# sb-sonata-fpgaio2.net
KiCad netlist of a schematic drawn in Altium Designer
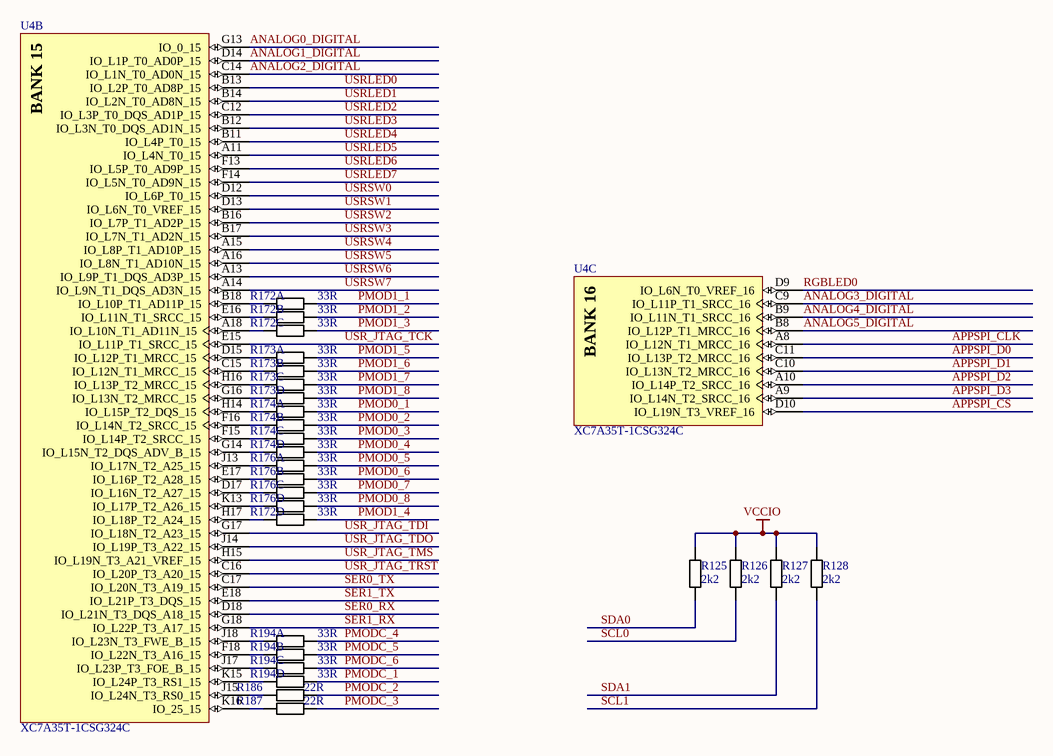
[diagram p0: sb-sonata-fpgaio2.SchDoc]

(export (version "E")
  (design (tool "Eeschema 10.0.6"))
  (components
    (comp (ref "R125")
      (value "2k2")
      (footprint "RESC1608X55N")
      (description "2k2 res, 0603, 1%, 1/10W")
      (fields (field (name "PART NUMBER") "RCHIP-2K2-0603") (field (name "TOLERANCE") "1%"))
      (libsource (lib "NewAE_AltiumLib") (part "RES-EU"))
    )
    (comp (ref "R126")
      (value "2k2")
      (footprint "RESC1608X55N")
      (description "2k2 res, 0603, 1%, 1/10W")
      (fields (field (name "PART NUMBER") "RCHIP-2K2-0603") (field (name "TOLERANCE") "1%"))
      (libsource (lib "NewAE_AltiumLib") (part "RES-EU"))
    )
    (comp (ref "R127")
      (value "2k2")
      (footprint "RESC1608X55N")
      (description "2k2 res, 0603, 1%, 1/10W")
      (fields (field (name "PART NUMBER") "RCHIP-2K2-0603") (field (name "TOLERANCE") "1%"))
      (libsource (lib "NewAE_AltiumLib") (part "RES-EU"))
    )
    (comp (ref "R128")
      (value "2k2")
      (footprint "RESC1608X55N")
      (description "2k2 res, 0603, 1%, 1/10W")
      (fields (field (name "PART NUMBER") "RCHIP-2K2-0603") (field (name "TOLERANCE") "1%"))
      (libsource (lib "NewAE_AltiumLib") (part "RES-EU"))
    )
    (comp (ref "R172")
      (value "33R")
      (footprint "741C083")
      (description "33-ohm, 0.5mm res array")
      (fields (field (name "PART NUMBER") "741C083330JP"))
      (libsource (lib "NewAE_AltiumLib") (part "RES-EU-4ARRAY"))
    )
    (comp (ref "R173")
      (value "33R")
      (footprint "741C083")
      (description "33-ohm, 0.5mm res array")
      (fields (field (name "PART NUMBER") "741C083330JP"))
      (libsource (lib "NewAE_AltiumLib") (part "RES-EU-4ARRAY"))
    )
    (comp (ref "R174")
      (value "33R")
      (footprint "741C083")
      (description "33-ohm, 0.5mm res array")
      (fields (field (name "PART NUMBER") "741C083330JP"))
      (libsource (lib "NewAE_AltiumLib") (part "RES-EU-4ARRAY"))
    )
    (comp (ref "R176")
      (value "33R")
      (footprint "741C083")
      (description "33-ohm, 0.5mm res array")
      (fields (field (name "PART NUMBER") "741C083330JP"))
      (libsource (lib "NewAE_AltiumLib") (part "RES-EU-4ARRAY"))
    )
    (comp (ref "R186")
      (value "22R")
      (footprint "RESC1005X40N")
      (description "22R res, 0402, 1%, 1/16W")
      (fields (field (name "PART NUMBER") "RCHIP-22R-0402") (field (name "TOLERANCE") "1%"))
      (libsource (lib "") (part "RES-EU_1"))
    )
    (comp (ref "R187")
      (value "22R")
      (footprint "RESC1005X40N")
      (description "22R res, 0402, 1%, 1/16W")
      (fields (field (name "PART NUMBER") "RCHIP-22R-0402") (field (name "TOLERANCE") "1%"))
      (libsource (lib "") (part "RES-EU_1"))
    )
    (comp (ref "R194")
      (value "33R")
      (footprint "741C083")
      (description "33-ohm, 0.5mm res array")
      (fields (field (name "PART NUMBER") "741C083330JP"))
      (libsource (lib "NewAE_AltiumLib") (part "RES-EU-4ARRAY"))
    )
    (comp (ref "U4")
      (value "XC7A35T-1CSG324C")
      (footprint "CSG324")
      (description "Artix-7 FPGA, 210 User I/Os, 0 GTP, 324-Ball BGA, Speed Grade 1, Commercial Grade, Pb-Free")
      (fields (field (name "MANUFACTURER") "Xilinx"))
      (libsource (lib "") (part "XLNX-XC7A35T-CSG324_1"))
    )
  )
  (nets
    (net (code "1") (name "/ANALOG0_DIGITAL") (class "Default")
      (node (ref "U4") (pin "G13") (pinfunction "IO_0_15_G13") (pintype "bidirectional"))
    )
    (net (code "2") (name "/ANALOG1_DIGITAL") (class "Default")
      (node (ref "U4") (pin "D14") (pinfunction "IO_L1P_T0_AD0P_15_D14") (pintype "bidirectional"))
    )
    (net (code "3") (name "/ANALOG2_DIGITAL") (class "Default")
      (node (ref "U4") (pin "C14") (pinfunction "IO_L1N_T0_AD0N_15_C14") (pintype "bidirectional"))
    )
    (net (code "4") (name "/ANALOG3_DIGITAL") (class "Default")
      (node (ref "U4") (pin "C9") (pinfunction "IO_L11P_T1_SRCC_16_C9") (pintype "bidirectional"))
    )
    (net (code "5") (name "/ANALOG4_DIGITAL") (class "Default")
      (node (ref "U4") (pin "B9") (pinfunction "IO_L11N_T1_SRCC_16_B9") (pintype "bidirectional"))
    )
    (net (code "6") (name "/ANALOG5_DIGITAL") (class "Default")
      (node (ref "U4") (pin "B8") (pinfunction "IO_L12P_T1_MRCC_16_B8") (pintype "bidirectional"))
    )
    (net (code "7") (name "/APPSPI_CLK") (class "Default")
      (node (ref "U4") (pin "A8") (pinfunction "IO_L12N_T1_MRCC_16_A8") (pintype "bidirectional"))
    )
    (net (code "8") (name "/APPSPI_CS") (class "Default")
      (node (ref "U4") (pin "D10") (pinfunction "IO_L19N_T3_VREF_16_D10") (pintype "bidirectional"))
    )
    (net (code "9") (name "/APPSPI_D0") (class "Default")
      (node (ref "U4") (pin "C11") (pinfunction "IO_L13P_T2_MRCC_16_C11") (pintype "bidirectional"))
    )
    (net (code "10") (name "/APPSPI_D1") (class "Default")
      (node (ref "U4") (pin "C10") (pinfunction "IO_L13N_T2_MRCC_16_C10") (pintype "bidirectional"))
    )
    (net (code "11") (name "/APPSPI_D2") (class "Default")
      (node (ref "U4") (pin "A10") (pinfunction "IO_L14P_T2_SRCC_16_A10") (pintype "bidirectional"))
    )
    (net (code "12") (name "/APPSPI_D3") (class "Default")
      (node (ref "U4") (pin "A9") (pinfunction "IO_L14N_T2_SRCC_16_A9") (pintype "bidirectional"))
    )
    (net (code "13") (name "/PMOD0_1") (class "Default")
      (node (ref "R174") (pin "1B") (pinfunction "1B_1B") (pintype "passive"))
    )
    (net (code "14") (name "/PMOD0_2") (class "Default")
      (node (ref "R174") (pin "2B") (pinfunction "2B_2B") (pintype "passive"))
    )
    (net (code "15") (name "/PMOD0_3") (class "Default")
      (node (ref "R174") (pin "3B") (pinfunction "3B_3B") (pintype "passive"))
    )
    (net (code "16") (name "/PMOD0_4") (class "Default")
      (node (ref "R174") (pin "4B") (pinfunction "4B_4B") (pintype "passive"))
    )
    (net (code "17") (name "/PMOD0_5") (class "Default")
      (node (ref "R176") (pin "1B") (pinfunction "1B_1B") (pintype "passive"))
    )
    (net (code "18") (name "/PMOD0_6") (class "Default")
      (node (ref "R176") (pin "2B") (pinfunction "2B_2B") (pintype "passive"))
    )
    (net (code "19") (name "/PMOD0_7") (class "Default")
      (node (ref "R176") (pin "3B") (pinfunction "3B_3B") (pintype "passive"))
    )
    (net (code "20") (name "/PMOD0_8") (class "Default")
      (node (ref "R176") (pin "4B") (pinfunction "4B_4B") (pintype "passive"))
    )
    (net (code "21") (name "/PMOD1_1") (class "Default")
      (node (ref "R172") (pin "1B") (pinfunction "1B_1B") (pintype "passive"))
    )
    (net (code "22") (name "/PMOD1_2") (class "Default")
      (node (ref "R172") (pin "2B") (pinfunction "2B_2B") (pintype "passive"))
    )
    (net (code "23") (name "/PMOD1_3") (class "Default")
      (node (ref "R172") (pin "3B") (pinfunction "3B_3B") (pintype "passive"))
    )
    (net (code "24") (name "/PMOD1_4") (class "Default")
      (node (ref "R172") (pin "4B") (pinfunction "4B_4B") (pintype "passive"))
    )
    (net (code "25") (name "/PMOD1_5") (class "Default")
      (node (ref "R173") (pin "1B") (pinfunction "1B_1B") (pintype "passive"))
    )
    (net (code "26") (name "/PMOD1_6") (class "Default")
      (node (ref "R173") (pin "2B") (pinfunction "2B_2B") (pintype "passive"))
    )
    (net (code "27") (name "/PMOD1_7") (class "Default")
      (node (ref "R173") (pin "3B") (pinfunction "3B_3B") (pintype "passive"))
    )
    (net (code "28") (name "/PMOD1_8") (class "Default")
      (node (ref "R173") (pin "4B") (pinfunction "4B_4B") (pintype "passive"))
    )
    (net (code "29") (name "/PMODC_1") (class "Default")
      (node (ref "R194") (pin "4B") (pinfunction "4B_4B") (pintype "passive"))
    )
    (net (code "30") (name "/PMODC_2") (class "Default")
      (node (ref "R186") (pin "2") (pinfunction "2_2") (pintype "passive"))
    )
    (net (code "31") (name "/PMODC_3") (class "Default")
      (node (ref "R187") (pin "2") (pinfunction "2_2") (pintype "passive"))
    )
    (net (code "32") (name "/PMODC_4") (class "Default")
      (node (ref "R194") (pin "1B") (pinfunction "1B_1B") (pintype "passive"))
    )
    (net (code "33") (name "/PMODC_5") (class "Default")
      (node (ref "R194") (pin "2B") (pinfunction "2B_2B") (pintype "passive"))
    )
    (net (code "34") (name "/PMODC_6") (class "Default")
      (node (ref "R194") (pin "3B") (pinfunction "3B_3B") (pintype "passive"))
    )
    (net (code "35") (name "/RGBLED0") (class "Default")
      (node (ref "U4") (pin "D9") (pinfunction "IO_L6N_T0_VREF_16_D9") (pintype "bidirectional"))
    )
    (net (code "36") (name "/SCL0") (class "Default")
      (node (ref "R126") (pin "2") (pinfunction "2_2") (pintype "passive"))
    )
    (net (code "37") (name "/SCL1") (class "Default")
      (node (ref "R128") (pin "2") (pinfunction "2_2") (pintype "passive"))
    )
    (net (code "38") (name "/SDA0") (class "Default")
      (node (ref "R125") (pin "2") (pinfunction "2_2") (pintype "passive"))
    )
    (net (code "39") (name "/SDA1") (class "Default")
      (node (ref "R127") (pin "2") (pinfunction "2_2") (pintype "passive"))
    )
    (net (code "40") (name "/SER0_RX") (class "Default")
      (node (ref "U4") (pin "D18") (pinfunction "IO_L21N_T3_DQS_A18_15_D18") (pintype "bidirectional"))
    )
    (net (code "41") (name "/SER0_TX") (class "Default")
      (node (ref "U4") (pin "C17") (pinfunction "IO_L20N_T3_A19_15_C17") (pintype "bidirectional"))
    )
    (net (code "42") (name "/SER1_RX") (class "Default")
      (node (ref "U4") (pin "G18") (pinfunction "IO_L22P_T3_A17_15_G18") (pintype "bidirectional"))
    )
    (net (code "43") (name "/SER1_TX") (class "Default")
      (node (ref "U4") (pin "E18") (pinfunction "IO_L21P_T3_DQS_15_E18") (pintype "bidirectional"))
    )
    (net (code "44") (name "/USRLED0") (class "Default")
      (node (ref "U4") (pin "B13") (pinfunction "IO_L2P_T0_AD8P_15_B13") (pintype "bidirectional"))
    )
    (net (code "45") (name "/USRLED1") (class "Default")
      (node (ref "U4") (pin "B14") (pinfunction "IO_L2N_T0_AD8N_15_B14") (pintype "bidirectional"))
    )
    (net (code "46") (name "/USRLED2") (class "Default")
      (node (ref "U4") (pin "C12") (pinfunction "IO_L3P_T0_DQS_AD1P_15_C12") (pintype "bidirectional"))
    )
    (net (code "47") (name "/USRLED3") (class "Default")
      (node (ref "U4") (pin "B12") (pinfunction "IO_L3N_T0_DQS_AD1N_15_B12") (pintype "bidirectional"))
    )
    (net (code "48") (name "/USRLED4") (class "Default")
      (node (ref "U4") (pin "B11") (pinfunction "IO_L4P_T0_15_B11") (pintype "bidirectional"))
    )
    (net (code "49") (name "/USRLED5") (class "Default")
      (node (ref "U4") (pin "A11") (pinfunction "IO_L4N_T0_15_A11") (pintype "bidirectional"))
    )
    (net (code "50") (name "/USRLED6") (class "Default")
      (node (ref "U4") (pin "F13") (pinfunction "IO_L5P_T0_AD9P_15_F13") (pintype "bidirectional"))
    )
    (net (code "51") (name "/USRLED7") (class "Default")
      (node (ref "U4") (pin "F14") (pinfunction "IO_L5N_T0_AD9N_15_F14") (pintype "bidirectional"))
    )
    (net (code "52") (name "/USRSW0") (class "Default")
      (node (ref "U4") (pin "D12") (pinfunction "IO_L6P_T0_15_D12") (pintype "bidirectional"))
    )
    (net (code "53") (name "/USRSW1") (class "Default")
      (node (ref "U4") (pin "D13") (pinfunction "IO_L6N_T0_VREF_15_D13") (pintype "bidirectional"))
    )
    (net (code "54") (name "/USRSW2") (class "Default")
      (node (ref "U4") (pin "B16") (pinfunction "IO_L7P_T1_AD2P_15_B16") (pintype "bidirectional"))
    )
    (net (code "55") (name "/USRSW3") (class "Default")
      (node (ref "U4") (pin "B17") (pinfunction "IO_L7N_T1_AD2N_15_B17") (pintype "bidirectional"))
    )
    (net (code "56") (name "/USRSW4") (class "Default")
      (node (ref "U4") (pin "A15") (pinfunction "IO_L8P_T1_AD10P_15_A15") (pintype "bidirectional"))
    )
    (net (code "57") (name "/USRSW5") (class "Default")
      (node (ref "U4") (pin "A16") (pinfunction "IO_L8N_T1_AD10N_15_A16") (pintype "bidirectional"))
    )
    (net (code "58") (name "/USRSW6") (class "Default")
      (node (ref "U4") (pin "A13") (pinfunction "IO_L9P_T1_DQS_AD3P_15_A13") (pintype "bidirectional"))
    )
    (net (code "59") (name "/USRSW7") (class "Default")
      (node (ref "U4") (pin "A14") (pinfunction "IO_L9N_T1_DQS_AD3N_15_A14") (pintype "bidirectional"))
    )
    (net (code "60") (name "/USR_JTAG_TCK") (class "Default")
      (node (ref "U4") (pin "E15") (pinfunction "IO_L11P_T1_SRCC_15_E15") (pintype "bidirectional"))
    )
    (net (code "61") (name "/USR_JTAG_TDI") (class "Default")
      (node (ref "U4") (pin "G17") (pinfunction "IO_L18N_T2_A23_15_G17") (pintype "bidirectional"))
    )
    (net (code "62") (name "/USR_JTAG_TDO") (class "Default")
      (node (ref "U4") (pin "J14") (pinfunction "IO_L19P_T3_A22_15_J14") (pintype "bidirectional"))
    )
    (net (code "63") (name "/USR_JTAG_TMS") (class "Default")
      (node (ref "U4") (pin "H15") (pinfunction "IO_L19N_T3_A21_VREF_15_H15") (pintype "bidirectional"))
    )
    (net (code "64") (name "/USR_JTAG_TRST") (class "Default")
      (node (ref "U4") (pin "C16") (pinfunction "IO_L20P_T3_A20_15_C16") (pintype "bidirectional"))
    )
    (net (code "65") (name "Net-(U4B-IO_25_15)") (class "Default")
      (node (ref "R187") (pin "1") (pinfunction "1_1") (pintype "passive"))
      (node (ref "U4") (pin "K16") (pinfunction "IO_25_15_K16") (pintype "bidirectional"))
    )
    (net (code "66") (name "Net-(U4B-IO_L10N_T1_AD11N_15)") (class "Default")
      (node (ref "R172") (pin "3A") (pinfunction "3A_3A") (pintype "passive"))
      (node (ref "U4") (pin "A18") (pinfunction "IO_L10N_T1_AD11N_15_A18") (pintype "bidirectional"))
    )
    (net (code "67") (name "Net-(U4B-IO_L10P_T1_AD11P_15)") (class "Default")
      (node (ref "R172") (pin "1A") (pinfunction "1A_1A") (pintype "passive"))
      (node (ref "U4") (pin "B18") (pinfunction "IO_L10P_T1_AD11P_15_B18") (pintype "bidirectional"))
    )
    (net (code "68") (name "Net-(U4B-IO_L11N_T1_SRCC_15)") (class "Default")
      (node (ref "R172") (pin "2A") (pinfunction "2A_2A") (pintype "passive"))
      (node (ref "U4") (pin "E16") (pinfunction "IO_L11N_T1_SRCC_15_E16") (pintype "bidirectional"))
    )
    (net (code "69") (name "Net-(U4B-IO_L12N_T1_MRCC_15)") (class "Default")
      (node (ref "R173") (pin "2A") (pinfunction "2A_2A") (pintype "passive"))
      (node (ref "U4") (pin "C15") (pinfunction "IO_L12N_T1_MRCC_15_C15") (pintype "bidirectional"))
    )
    (net (code "70") (name "Net-(U4B-IO_L12P_T1_MRCC_15)") (class "Default")
      (node (ref "R173") (pin "1A") (pinfunction "1A_1A") (pintype "passive"))
      (node (ref "U4") (pin "D15") (pinfunction "IO_L12P_T1_MRCC_15_D15") (pintype "bidirectional"))
    )
    (net (code "71") (name "Net-(U4B-IO_L13N_T2_MRCC_15)") (class "Default")
      (node (ref "R173") (pin "4A") (pinfunction "4A_4A") (pintype "passive"))
      (node (ref "U4") (pin "G16") (pinfunction "IO_L13N_T2_MRCC_15_G16") (pintype "bidirectional"))
    )
    (net (code "72") (name "Net-(U4B-IO_L13P_T2_MRCC_15)") (class "Default")
      (node (ref "R173") (pin "3A") (pinfunction "3A_3A") (pintype "passive"))
      (node (ref "U4") (pin "H16") (pinfunction "IO_L13P_T2_MRCC_15_H16") (pintype "bidirectional"))
    )
    (net (code "73") (name "Net-(U4B-IO_L14N_T2_SRCC_15)") (class "Default")
      (node (ref "R174") (pin "2A") (pinfunction "2A_2A") (pintype "passive"))
      (node (ref "U4") (pin "F16") (pinfunction "IO_L14N_T2_SRCC_15_F16") (pintype "bidirectional"))
    )
    (net (code "74") (name "Net-(U4B-IO_L14P_T2_SRCC_15)") (class "Default")
      (node (ref "R174") (pin "3A") (pinfunction "3A_3A") (pintype "passive"))
      (node (ref "U4") (pin "F15") (pinfunction "IO_L14P_T2_SRCC_15_F15") (pintype "bidirectional"))
    )
    (net (code "75") (name "Net-(U4B-IO_L15N_T2_DQS_ADV_B_15)") (class "Default")
      (node (ref "R174") (pin "4A") (pinfunction "4A_4A") (pintype "passive"))
      (node (ref "U4") (pin "G14") (pinfunction "IO_L15N_T2_DQS_ADV_B_15_G14") (pintype "bidirectional"))
    )
    (net (code "76") (name "Net-(U4B-IO_L15P_T2_DQS_15)") (class "Default")
      (node (ref "R174") (pin "1A") (pinfunction "1A_1A") (pintype "passive"))
      (node (ref "U4") (pin "H14") (pinfunction "IO_L15P_T2_DQS_15_H14") (pintype "bidirectional"))
    )
    (net (code "77") (name "Net-(U4B-IO_L16N_T2_A27_15)") (class "Default")
      (node (ref "R176") (pin "3A") (pinfunction "3A_3A") (pintype "passive"))
      (node (ref "U4") (pin "D17") (pinfunction "IO_L16N_T2_A27_15_D17") (pintype "bidirectional"))
    )
    (net (code "78") (name "Net-(U4B-IO_L16P_T2_A28_15)") (class "Default")
      (node (ref "R176") (pin "2A") (pinfunction "2A_2A") (pintype "passive"))
      (node (ref "U4") (pin "E17") (pinfunction "IO_L16P_T2_A28_15_E17") (pintype "bidirectional"))
    )
    (net (code "79") (name "Net-(U4B-IO_L17N_T2_A25_15)") (class "Default")
      (node (ref "R176") (pin "1A") (pinfunction "1A_1A") (pintype "passive"))
      (node (ref "U4") (pin "J13") (pinfunction "IO_L17N_T2_A25_15_J13") (pintype "bidirectional"))
    )
    (net (code "80") (name "Net-(U4B-IO_L17P_T2_A26_15)") (class "Default")
      (node (ref "R176") (pin "4A") (pinfunction "4A_4A") (pintype "passive"))
      (node (ref "U4") (pin "K13") (pinfunction "IO_L17P_T2_A26_15_K13") (pintype "bidirectional"))
    )
    (net (code "81") (name "Net-(U4B-IO_L18P_T2_A24_15)") (class "Default")
      (node (ref "R172") (pin "4A") (pinfunction "4A_4A") (pintype "passive"))
      (node (ref "U4") (pin "H17") (pinfunction "IO_L18P_T2_A24_15_H17") (pintype "bidirectional"))
    )
    (net (code "82") (name "Net-(U4B-IO_L22N_T3_A16_15)") (class "Default")
      (node (ref "R194") (pin "2A") (pinfunction "2A_2A") (pintype "passive"))
      (node (ref "U4") (pin "F18") (pinfunction "IO_L22N_T3_A16_15_F18") (pintype "bidirectional"))
    )
    (net (code "83") (name "Net-(U4B-IO_L23N_T3_FWE_B_15)") (class "Default")
      (node (ref "R194") (pin "1A") (pinfunction "1A_1A") (pintype "passive"))
      (node (ref "U4") (pin "J18") (pinfunction "IO_L23N_T3_FWE_B_15_J18") (pintype "bidirectional"))
    )
    (net (code "84") (name "Net-(U4B-IO_L23P_T3_FOE_B_15)") (class "Default")
      (node (ref "R194") (pin "3A") (pinfunction "3A_3A") (pintype "passive"))
      (node (ref "U4") (pin "J17") (pinfunction "IO_L23P_T3_FOE_B_15_J17") (pintype "bidirectional"))
    )
    (net (code "85") (name "Net-(U4B-IO_L24N_T3_RS0_15)") (class "Default")
      (node (ref "R186") (pin "1") (pinfunction "1_1") (pintype "passive"))
      (node (ref "U4") (pin "J15") (pinfunction "IO_L24N_T3_RS0_15_J15") (pintype "bidirectional"))
    )
    (net (code "86") (name "Net-(U4B-IO_L24P_T3_RS1_15)") (class "Default")
      (node (ref "R194") (pin "4A") (pinfunction "4A_4A") (pintype "passive"))
      (node (ref "U4") (pin "K15") (pinfunction "IO_L24P_T3_RS1_15_K15") (pintype "bidirectional"))
    )
    (net (code "87") (name "VCCIO") (class "Default")
      (node (ref "R125") (pin "1") (pinfunction "1_1") (pintype "passive"))
      (node (ref "R126") (pin "1") (pinfunction "1_1") (pintype "passive"))
      (node (ref "R127") (pin "1") (pinfunction "1_1") (pintype "passive"))
      (node (ref "R128") (pin "1") (pinfunction "1_1") (pintype "passive"))
    )
  )
)
